# odrs_redraw.net
KiCad netlist of a schematic drawn in EAGLE
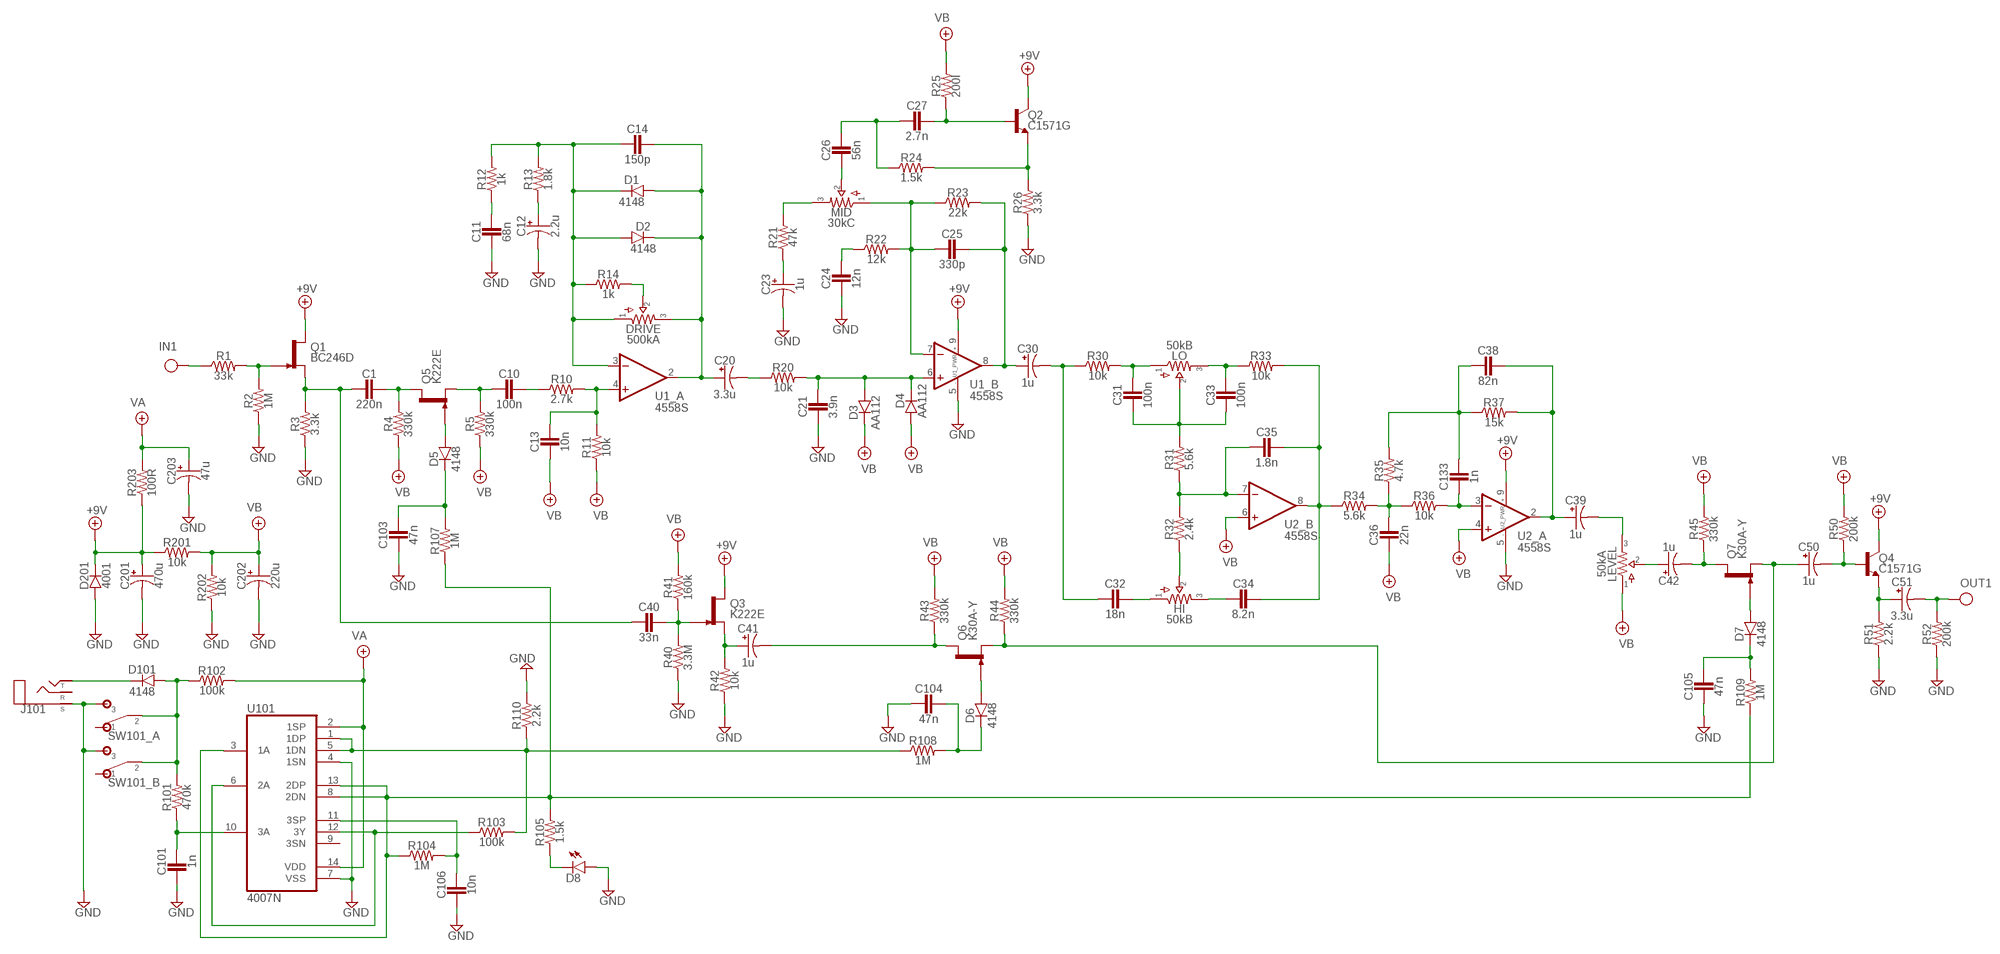
[diagram p0: schematic, sheet 1]

(export (version "E")
  (design (tool "Eeschema 10.0.6"))
  (components
    (comp (ref "C1")
      (value "220n")
      (footprint "eagle-import:BOX_SMALL")
      (libsource (lib "eagle-import") (part "CER/FILMBOX.1"))
    )
    (comp (ref "C10")
      (value "100n")
      (footprint "eagle-import:BOX_SMALL")
      (libsource (lib "eagle-import") (part "CER/FILMBOX.1"))
    )
    (comp (ref "C11")
      (value "68n")
      (footprint "eagle-import:BOX_SMALL")
      (libsource (lib "eagle-import") (part "CER/FILMBOX.1"))
    )
    (comp (ref "C12")
      (value "2.2u")
      (footprint "eagle-import:050_020")
      (libsource (lib "eagle-import") (part "0500"))
    )
    (comp (ref "C13")
      (value "10n")
      (footprint "eagle-import:BOX_SMALL")
      (libsource (lib "eagle-import") (part "CER/FILMBOX.1"))
    )
    (comp (ref "C14")
      (value "150p")
      (footprint "eagle-import:BOX_SMALL")
      (libsource (lib "eagle-import") (part "CER/FILMBOX.1"))
    )
    (comp (ref "C20")
      (value "3.3u")
      (footprint "eagle-import:050_020")
      (libsource (lib "eagle-import") (part "0500"))
    )
    (comp (ref "C21")
      (value "3.9n")
      (footprint "eagle-import:BOX_SMALL")
      (libsource (lib "eagle-import") (part "CER/FILMBOX.1"))
    )
    (comp (ref "C23")
      (value "1u")
      (footprint "eagle-import:050_020")
      (libsource (lib "eagle-import") (part "0500"))
    )
    (comp (ref "C24")
      (value "12n")
      (footprint "eagle-import:BOX_SMALL")
      (libsource (lib "eagle-import") (part "CER/FILMBOX.1"))
    )
    (comp (ref "C25")
      (value "330p")
      (footprint "eagle-import:BOX_SMALL")
      (libsource (lib "eagle-import") (part "CER/FILMBOX.1"))
    )
    (comp (ref "C26")
      (value "56n")
      (footprint "eagle-import:BOX_SMALL")
      (libsource (lib "eagle-import") (part "CER/FILMBOX.1"))
    )
    (comp (ref "C27")
      (value "2.7n")
      (footprint "eagle-import:BOX_SMALL")
      (libsource (lib "eagle-import") (part "CER/FILMBOX.1"))
    )
    (comp (ref "C30")
      (value "1u")
      (footprint "eagle-import:050_020")
      (libsource (lib "eagle-import") (part "0500"))
    )
    (comp (ref "C31")
      (value "100n")
      (footprint "eagle-import:BOX_SMALL")
      (libsource (lib "eagle-import") (part "CER/FILMBOX.1"))
    )
    (comp (ref "C32")
      (value "18n")
      (footprint "eagle-import:BOX_SMALL")
      (libsource (lib "eagle-import") (part "CER/FILMBOX.1"))
    )
    (comp (ref "C33")
      (value "100n")
      (footprint "eagle-import:BOX_SMALL")
      (libsource (lib "eagle-import") (part "CER/FILMBOX.1"))
    )
    (comp (ref "C34")
      (value "8.2n")
      (footprint "eagle-import:BOX_SMALL")
      (libsource (lib "eagle-import") (part "CER/FILMBOX.1"))
    )
    (comp (ref "C35")
      (value "1.8n")
      (footprint "eagle-import:BOX_SMALL")
      (libsource (lib "eagle-import") (part "CER/FILMBOX.1"))
    )
    (comp (ref "C36")
      (value "22n")
      (footprint "eagle-import:BOX_SMALL")
      (libsource (lib "eagle-import") (part "CER/FILMBOX.1"))
    )
    (comp (ref "C38")
      (value "82n")
      (footprint "eagle-import:BOX_SMALL")
      (libsource (lib "eagle-import") (part "CER/FILMBOX.1"))
    )
    (comp (ref "C39")
      (value "1u")
      (footprint "eagle-import:050_020")
      (libsource (lib "eagle-import") (part "0500"))
    )
    (comp (ref "C40")
      (value "33n")
      (footprint "eagle-import:BOX_SMALL")
      (libsource (lib "eagle-import") (part "CER/FILMBOX.1"))
    )
    (comp (ref "C41")
      (value "1u")
      (footprint "eagle-import:050_020")
      (libsource (lib "eagle-import") (part "0500"))
    )
    (comp (ref "C42")
      (value "1u")
      (footprint "eagle-import:050_020")
      (libsource (lib "eagle-import") (part "0500"))
    )
    (comp (ref "C50")
      (value "1u")
      (footprint "eagle-import:050_020")
      (libsource (lib "eagle-import") (part "0500"))
    )
    (comp (ref "C51")
      (value "3.3u")
      (footprint "eagle-import:050_020")
      (libsource (lib "eagle-import") (part "0500"))
    )
    (comp (ref "C101")
      (value "1n")
      (footprint "eagle-import:BOX_SMALL")
      (libsource (lib "eagle-import") (part "CER/FILMBOX.1"))
    )
    (comp (ref "C103")
      (value "47n")
      (footprint "eagle-import:BOX_SMALL")
      (libsource (lib "eagle-import") (part "CER/FILMBOX.1"))
    )
    (comp (ref "C104")
      (value "47n")
      (footprint "eagle-import:BOX_SMALL")
      (libsource (lib "eagle-import") (part "CER/FILMBOX.1"))
    )
    (comp (ref "C105")
      (value "47n")
      (footprint "eagle-import:BOX_SMALL")
      (libsource (lib "eagle-import") (part "CER/FILMBOX.1"))
    )
    (comp (ref "C106")
      (value "10n")
      (footprint "eagle-import:BOX_SMALL")
      (libsource (lib "eagle-import") (part "CER/FILMBOX.1"))
    )
    (comp (ref "C133")
      (value "1n")
      (footprint "eagle-import:BOX_SMALL")
      (libsource (lib "eagle-import") (part "CER/FILMBOX.1"))
    )
    (comp (ref "C201")
      (value "470u")
      (footprint "eagle-import:040_020")
      (libsource (lib "eagle-import") (part "0400"))
    )
    (comp (ref "C202")
      (value "220u")
      (footprint "eagle-import:040_020")
      (libsource (lib "eagle-import") (part "0400"))
    )
    (comp (ref "C203")
      (value "47u")
      (footprint "eagle-import:040_020")
      (libsource (lib "eagle-import") (part "0400"))
    )
    (comp (ref "D1")
      (value "4148")
      (footprint "eagle-import:DO35-2")
      (libsource (lib "eagle-import") (part "DO35.2"))
    )
    (comp (ref "D2")
      (value "4148")
      (footprint "eagle-import:DO35-2")
      (libsource (lib "eagle-import") (part "DO35.2"))
    )
    (comp (ref "D3")
      (value "AA112")
      (footprint "eagle-import:DO35-2")
      (libsource (lib "eagle-import") (part "DO35.2"))
    )
    (comp (ref "D4")
      (value "AA112")
      (footprint "eagle-import:DO35-2")
      (libsource (lib "eagle-import") (part "DO35.2"))
    )
    (comp (ref "D5")
      (value "4148")
      (footprint "eagle-import:DO35-2")
      (libsource (lib "eagle-import") (part "DO35.2"))
    )
    (comp (ref "D6")
      (value "4148")
      (footprint "eagle-import:DO35-2")
      (libsource (lib "eagle-import") (part "DO35.2"))
    )
    (comp (ref "D7")
      (value "4148")
      (footprint "eagle-import:DO35-2")
      (libsource (lib "eagle-import") (part "DO35.2"))
    )
    (comp (ref "D8")
      (value "LED")
      (footprint "eagle-import:3MM_D")
      (libsource (lib "eagle-import") (part "LED"))
    )
    (comp (ref "D101")
      (value "4148")
      (footprint "eagle-import:DO35-2")
      (libsource (lib "eagle-import") (part "DO35.2"))
    )
    (comp (ref "D201")
      (value "4001")
      (footprint "eagle-import:DO35-2")
      (libsource (lib "eagle-import") (part "DO35.2"))
    )
    (comp (ref "DRIVE")
      (value "500kA")
      (footprint "eagle-import:16MM")
      (libsource (lib "eagle-import") (part "POTS16MM"))
    )
    (comp (ref "HI")
      (value "50kB")
      (footprint "eagle-import:16MM")
      (libsource (lib "eagle-import") (part "POTS16MM"))
    )
    (comp (ref "J101")
      (value "STEREO3PADS")
      (footprint "eagle-import:THREEPADS")
      (libsource (lib "eagle-import") (part "STEREO3PADS"))
    )
    (comp (ref "LEVEL")
      (value "50kA")
      (footprint "eagle-import:16MM")
      (libsource (lib "eagle-import") (part "POTS16MM"))
    )
    (comp (ref "LO")
      (value "50kB")
      (footprint "eagle-import:16MM")
      (libsource (lib "eagle-import") (part "POTS16MM"))
    )
    (comp (ref "MID")
      (value "30kC")
      (footprint "eagle-import:16MM")
      (libsource (lib "eagle-import") (part "POTS16MM"))
    )
    (comp (ref "Q1")
      (value "BC246D")
      (footprint "eagle-import:TO92-")
      (libsource (lib "eagle-import") (part "2SK170"))
    )
    (comp (ref "Q2")
      (value "C1571G")
      (footprint "eagle-import:TO92-")
      (libsource (lib "eagle-import") (part "2N3904"))
    )
    (comp (ref "Q3")
      (value "K222E")
      (footprint "eagle-import:TO92-")
      (libsource (lib "eagle-import") (part "2SK170"))
    )
    (comp (ref "Q4")
      (value "C1571G")
      (footprint "eagle-import:TO92-")
      (libsource (lib "eagle-import") (part "2N3904"))
    )
    (comp (ref "Q5")
      (value "K222E")
      (footprint "eagle-import:TO92-")
      (libsource (lib "eagle-import") (part "2SK170"))
    )
    (comp (ref "Q6")
      (value "K30A-Y")
      (footprint "eagle-import:TO92-")
      (libsource (lib "eagle-import") (part "2SK170"))
    )
    (comp (ref "Q7")
      (value "K30A-Y")
      (footprint "eagle-import:TO92-")
      (libsource (lib "eagle-import") (part "2SK170"))
    )
    (comp (ref "R1")
      (value "33k")
      (footprint "eagle-import:R0207_3")
      (libsource (lib "eagle-import") (part "R_.3B"))
    )
    (comp (ref "R2")
      (value "1M")
      (footprint "eagle-import:R0207_3")
      (libsource (lib "eagle-import") (part "R_.3B"))
    )
    (comp (ref "R3")
      (value "3.3k")
      (footprint "eagle-import:R0207_3")
      (libsource (lib "eagle-import") (part "R_.3B"))
    )
    (comp (ref "R4")
      (value "330k")
      (footprint "eagle-import:R0207_3")
      (libsource (lib "eagle-import") (part "R_.3B"))
    )
    (comp (ref "R5")
      (value "330k")
      (footprint "eagle-import:R0207_3")
      (libsource (lib "eagle-import") (part "R_.3B"))
    )
    (comp (ref "R10")
      (value "2.7k")
      (footprint "eagle-import:R0207_3")
      (libsource (lib "eagle-import") (part "R_.3B"))
    )
    (comp (ref "R11")
      (value "10k")
      (footprint "eagle-import:R0207_3")
      (libsource (lib "eagle-import") (part "R_.3B"))
    )
    (comp (ref "R12")
      (value "1k")
      (footprint "eagle-import:R0207_3")
      (libsource (lib "eagle-import") (part "R_.3B"))
    )
    (comp (ref "R13")
      (value "1.8k")
      (footprint "eagle-import:R0207_3")
      (libsource (lib "eagle-import") (part "R_.3B"))
    )
    (comp (ref "R14")
      (value "1k")
      (footprint "eagle-import:R0207_3")
      (libsource (lib "eagle-import") (part "R_.3B"))
    )
    (comp (ref "R20")
      (value "10k")
      (footprint "eagle-import:R0207_3")
      (libsource (lib "eagle-import") (part "R_.3B"))
    )
    (comp (ref "R21")
      (value "47k")
      (footprint "eagle-import:R0207_3")
      (libsource (lib "eagle-import") (part "R_.3B"))
    )
    (comp (ref "R22")
      (value "12k")
      (footprint "eagle-import:R0207_3")
      (libsource (lib "eagle-import") (part "R_.3B"))
    )
    (comp (ref "R23")
      (value "22k")
      (footprint "eagle-import:R0207_3")
      (libsource (lib "eagle-import") (part "R_.3B"))
    )
    (comp (ref "R24")
      (value "1.5k")
      (footprint "eagle-import:R0207_3")
      (libsource (lib "eagle-import") (part "R_.3B"))
    )
    (comp (ref "R25")
      (value "200l")
      (footprint "eagle-import:R0207_3")
      (libsource (lib "eagle-import") (part "R_.3B"))
    )
    (comp (ref "R26")
      (value "3.3k")
      (footprint "eagle-import:R0207_3")
      (libsource (lib "eagle-import") (part "R_.3B"))
    )
    (comp (ref "R30")
      (value "10k")
      (footprint "eagle-import:R0207_3")
      (libsource (lib "eagle-import") (part "R_.3B"))
    )
    (comp (ref "R31")
      (value "5.6k")
      (footprint "eagle-import:R0207_3")
      (libsource (lib "eagle-import") (part "R_.3B"))
    )
    (comp (ref "R32")
      (value "2.4k")
      (footprint "eagle-import:R0207_3")
      (libsource (lib "eagle-import") (part "R_.3B"))
    )
    (comp (ref "R33")
      (value "10k")
      (footprint "eagle-import:R0207_3")
      (libsource (lib "eagle-import") (part "R_.3B"))
    )
    (comp (ref "R34")
      (value "5.6k")
      (footprint "eagle-import:R0207_3")
      (libsource (lib "eagle-import") (part "R_.3B"))
    )
    (comp (ref "R35")
      (value "4.7k")
      (footprint "eagle-import:R0207_3")
      (libsource (lib "eagle-import") (part "R_.3B"))
    )
    (comp (ref "R36")
      (value "10k")
      (footprint "eagle-import:R0207_3")
      (libsource (lib "eagle-import") (part "R_.3B"))
    )
    (comp (ref "R37")
      (value "15k")
      (footprint "eagle-import:R0207_3")
      (libsource (lib "eagle-import") (part "R_.3B"))
    )
    (comp (ref "R40")
      (value "3.3M")
      (footprint "eagle-import:R0207_3")
      (libsource (lib "eagle-import") (part "R_.3B"))
    )
    (comp (ref "R41")
      (value "160k")
      (footprint "eagle-import:R0207_3")
      (libsource (lib "eagle-import") (part "R_.3B"))
    )
    (comp (ref "R42")
      (value "10k")
      (footprint "eagle-import:R0207_3")
      (libsource (lib "eagle-import") (part "R_.3B"))
    )
    (comp (ref "R43")
      (value "330k")
      (footprint "eagle-import:R0207_3")
      (libsource (lib "eagle-import") (part "R_.3B"))
    )
    (comp (ref "R44")
      (value "330k")
      (footprint "eagle-import:R0207_3")
      (libsource (lib "eagle-import") (part "R_.3B"))
    )
    (comp (ref "R45")
      (value "330k")
      (footprint "eagle-import:R0207_3")
      (libsource (lib "eagle-import") (part "R_.3B"))
    )
    (comp (ref "R50")
      (value "200k")
      (footprint "eagle-import:R0207_3")
      (libsource (lib "eagle-import") (part "R_.3B"))
    )
    (comp (ref "R51")
      (value "2.2k")
      (footprint "eagle-import:R0207_3")
      (libsource (lib "eagle-import") (part "R_.3B"))
    )
    (comp (ref "R52")
      (value "200k")
      (footprint "eagle-import:R0207_3")
      (libsource (lib "eagle-import") (part "R_.3B"))
    )
    (comp (ref "R101")
      (value "470k")
      (footprint "eagle-import:R0207_3")
      (libsource (lib "eagle-import") (part "R_.3B"))
    )
    (comp (ref "R102")
      (value "100k")
      (footprint "eagle-import:R0207_3")
      (libsource (lib "eagle-import") (part "R_.3B"))
    )
    (comp (ref "R103")
      (value "100k")
      (footprint "eagle-import:R0207_3")
      (libsource (lib "eagle-import") (part "R_.3B"))
    )
    (comp (ref "R104")
      (value "1M")
      (footprint "eagle-import:R0207_3")
      (libsource (lib "eagle-import") (part "R_.3B"))
    )
    (comp (ref "R105")
      (value "1.5k")
      (footprint "eagle-import:R0207_3")
      (libsource (lib "eagle-import") (part "R_.3B"))
    )
    (comp (ref "R107")
      (value "1M")
      (footprint "eagle-import:R0207_3")
      (libsource (lib "eagle-import") (part "R_.3B"))
    )
    (comp (ref "R108")
      (value "1M")
      (footprint "eagle-import:R0207_3")
      (libsource (lib "eagle-import") (part "R_.3B"))
    )
    (comp (ref "R109")
      (value "1M")
      (footprint "eagle-import:R0207_3")
      (libsource (lib "eagle-import") (part "R_.3B"))
    )
    (comp (ref "R110")
      (value "2.2k")
      (footprint "eagle-import:R0207_3")
      (libsource (lib "eagle-import") (part "R_.3B"))
    )
    (comp (ref "R201")
      (value "10k")
      (footprint "eagle-import:R0207_3")
      (libsource (lib "eagle-import") (part "R_.3B"))
    )
    (comp (ref "R202")
      (value "10k")
      (footprint "eagle-import:R0207_3")
      (libsource (lib "eagle-import") (part "R_.3B"))
    )
    (comp (ref "R203")
      (value "100R")
      (footprint "eagle-import:R0207_3")
      (libsource (lib "eagle-import") (part "R_.3B"))
    )
    (comp (ref "SW101")
      (value "DPDT")
      (footprint "eagle-import:DPDT")
      (libsource (lib "eagle-import") (part "DPDT"))
    )
    (comp (ref "U1")
      (value "4558S")
      (footprint "eagle-import:SIL09")
      (libsource (lib "eagle-import") (part "DUAL"))
    )
    (comp (ref "U2")
      (value "4558S")
      (footprint "eagle-import:SIL09")
      (libsource (lib "eagle-import") (part "DUAL"))
    )
    (comp (ref "U101")
      (value "4007N")
      (footprint "eagle-import:DIL14")
      (libsource (lib "eagle-import") (part "4007N"))
    )
  )
  (nets
    (net (code "1") (name "+9V") (class "Default")
      (node (ref "C201") (pin "+") (pinfunction "+_+") (pintype "passive"))
      (node (ref "D201") (pin "C") (pinfunction "C_C") (pintype "passive"))
      (node (ref "Q1") (pin "3") (pinfunction "D_3") (pintype "passive"))
      (node (ref "Q2") (pin "1") (pinfunction "C_1") (pintype "passive"))
      (node (ref "Q3") (pin "3") (pinfunction "D_3") (pintype "passive"))
      (node (ref "Q4") (pin "1") (pinfunction "C_1") (pintype "passive"))
      (node (ref "R201") (pin "1") (pinfunction "1_1") (pintype "passive"))
      (node (ref "R203") (pin "1") (pinfunction "1_1") (pintype "passive"))
      (node (ref "U1") (pin "9") (pinfunction "V+_9") (pintype "power_in"))
      (node (ref "U2") (pin "9") (pinfunction "V+_9") (pintype "power_in"))
    )
    (net (code "2") (name "GND") (class "Default")
      (node (ref "C101") (pin "2") (pinfunction "2_2") (pintype "passive"))
      (node (ref "C103") (pin "2") (pinfunction "2_2") (pintype "passive"))
      (node (ref "C104") (pin "2") (pinfunction "2_2") (pintype "passive"))
      (node (ref "C105") (pin "2") (pinfunction "2_2") (pintype "passive"))
      (node (ref "C106") (pin "2") (pinfunction "2_2") (pintype "passive"))
      (node (ref "C11") (pin "2") (pinfunction "2_2") (pintype "passive"))
      (node (ref "C12") (pin "-") (pinfunction "-_-") (pintype "passive"))
      (node (ref "C201") (pin "-") (pinfunction "-_-") (pintype "passive"))
      (node (ref "C202") (pin "-") (pinfunction "-_-") (pintype "passive"))
      (node (ref "C203") (pin "-") (pinfunction "-_-") (pintype "passive"))
      (node (ref "C21") (pin "2") (pinfunction "2_2") (pintype "passive"))
      (node (ref "C23") (pin "-") (pinfunction "-_-") (pintype "passive"))
      (node (ref "C24") (pin "2") (pinfunction "2_2") (pintype "passive"))
      (node (ref "D201") (pin "A") (pinfunction "A_A") (pintype "passive"))
      (node (ref "D8") (pin "ANODE") (pinfunction "A_ANODE") (pintype "passive"))
      (node (ref "J101") (pin "SLEEVE") (pinfunction "S_SLEEVE") (pintype "passive"))
      (node (ref "R110") (pin "2") (pinfunction "2_2") (pintype "passive"))
      (node (ref "R2") (pin "1") (pinfunction "1_1") (pintype "passive"))
      (node (ref "R202") (pin "1") (pinfunction "1_1") (pintype "passive"))
      (node (ref "R26") (pin "1") (pinfunction "1_1") (pintype "passive"))
      (node (ref "R3") (pin "1") (pinfunction "1_1") (pintype "passive"))
      (node (ref "R40") (pin "1") (pinfunction "1_1") (pintype "passive"))
      (node (ref "R42") (pin "1") (pinfunction "1_1") (pintype "passive"))
      (node (ref "R51") (pin "1") (pinfunction "1_1") (pintype "passive"))
      (node (ref "R52") (pin "1") (pinfunction "1_1") (pintype "passive"))
      (node (ref "SW101") (pin "A3") (pinfunction "3_A3") (pintype "passive"))
      (node (ref "SW101") (pin "B3") (pinfunction "3_B3") (pintype "passive"))
      (node (ref "U1") (pin "5") (pinfunction "V-_5") (pintype "power_in"))
      (node (ref "U101") (pin "4") (pinfunction "1SN_4") (pintype "open_collector"))
      (node (ref "U101") (pin "7") (pinfunction "VSS_7") (pintype "input"))
      (node (ref "U2") (pin "5") (pinfunction "V-_5") (pintype "power_in"))
    )
    (net (code "3") (name "IN") (class "Default")
      (node (ref "R1") (pin "1") (pinfunction "1_1") (pintype "passive"))
    )
    (net (code "4") (name "Net-(C10-Pad1)") (class "Default")
      (node (ref "C10") (pin "1") (pinfunction "1_1") (pintype "passive"))
      (node (ref "R10") (pin "1") (pinfunction "1_1") (pintype "passive"))
    )
    (net (code "5") (name "Net-(C11-Pad1)") (class "Default")
      (node (ref "C11") (pin "1") (pinfunction "1_1") (pintype "passive"))
      (node (ref "R12") (pin "1") (pinfunction "1_1") (pintype "passive"))
    )
    (net (code "6") (name "Net-(C12-Pad+)") (class "Default")
      (node (ref "C12") (pin "+") (pinfunction "+_+") (pintype "passive"))
      (node (ref "R13") (pin "1") (pinfunction "1_1") (pintype "passive"))
    )
    (net (code "7") (name "Net-(C20-Pad-)") (class "Default")
      (node (ref "C20") (pin "-") (pinfunction "-_-") (pintype "passive"))
      (node (ref "R20") (pin "1") (pinfunction "1_1") (pintype "passive"))
    )
    (net (code "8") (name "Net-(C23-Pad+)") (class "Default")
      (node (ref "C23") (pin "+") (pinfunction "+_+") (pintype "passive"))
      (node (ref "R21") (pin "1") (pinfunction "1_1") (pintype "passive"))
    )
    (net (code "9") (name "Net-(C24-Pad1)") (class "Default")
      (node (ref "C24") (pin "1") (pinfunction "1_1") (pintype "passive"))
      (node (ref "R22") (pin "1") (pinfunction "1_1") (pintype "passive"))
    )
    (net (code "10") (name "Net-(C26-Pad1)") (class "Default")
      (node (ref "C26") (pin "1") (pinfunction "1_1") (pintype "passive"))
      (node (ref "C27") (pin "2") (pinfunction "2_2") (pintype "passive"))
      (node (ref "R24") (pin "1") (pinfunction "1_1") (pintype "passive"))
    )
    (net (code "11") (name "Net-(C26-Pad2)") (class "Default")
      (node (ref "C26") (pin "2") (pinfunction "2_2") (pintype "passive"))
      (node (ref "MID") (pin "2") (pinfunction "2_2") (pintype "passive"))
    )
    (net (code "12") (name "Net-(C30-Pad-)") (class "Default")
      (node (ref "C30") (pin "-") (pinfunction "-_-") (pintype "passive"))
      (node (ref "C32") (pin "2") (pinfunction "2_2") (pintype "passive"))
      (node (ref "R30") (pin "1") (pinfunction "1_1") (pintype "passive"))
    )
    (net (code "13") (name "Net-(C31-Pad1)") (class "Default")
      (node (ref "C31") (pin "1") (pinfunction "1_1") (pintype "passive"))
      (node (ref "LO") (pin "1") (pinfunction "1_1") (pintype "passive"))
      (node (ref "R30") (pin "2") (pinfunction "2_2") (pintype "passive"))
    )
    (net (code "14") (name "Net-(C31-Pad2)") (class "Default")
      (node (ref "C31") (pin "2") (pinfunction "2_2") (pintype "passive"))
      (node (ref "C33") (pin "2") (pinfunction "2_2") (pintype "passive"))
      (node (ref "LO") (pin "2") (pinfunction "2_2") (pintype "passive"))
      (node (ref "R31") (pin "2") (pinfunction "2_2") (pintype "passive"))
    )
    (net (code "15") (name "Net-(C32-Pad1)") (class "Default")
      (node (ref "C32") (pin "1") (pinfunction "1_1") (pintype "passive"))
      (node (ref "HI") (pin "1") (pinfunction "1_1") (pintype "passive"))
    )
    (net (code "16") (name "Net-(C33-Pad1)") (class "Default")
      (node (ref "C33") (pin "1") (pinfunction "1_1") (pintype "passive"))
      (node (ref "LO") (pin "3") (pinfunction "3_3") (pintype "passive"))
      (node (ref "R33") (pin "1") (pinfunction "1_1") (pintype "passive"))
    )
    (net (code "17") (name "Net-(C34-Pad2)") (class "Default")
      (node (ref "C34") (pin "2") (pinfunction "2_2") (pintype "passive"))
      (node (ref "HI") (pin "3") (pinfunction "3_3") (pintype "passive"))
    )
    (net (code "18") (name "Net-(C36-Pad1)") (class "Default")
      (node (ref "C36") (pin "1") (pinfunction "1_1") (pintype "passive"))
      (node (ref "R34") (pin "2") (pinfunction "2_2") (pintype "passive"))
      (node (ref "R35") (pin "1") (pinfunction "1_1") (pintype "passive"))
      (node (ref "R36") (pin "1") (pinfunction "1_1") (pintype "passive"))
    )
    (net (code "19") (name "Net-(C39-Pad-)") (class "Default")
      (node (ref "C39") (pin "-") (pinfunction "-_-") (pintype "passive"))
      (node (ref "LEVEL") (pin "3") (pinfunction "3_3") (pintype "passive"))
    )
    (net (code "20") (name "Net-(C42-Pad+)") (class "Default")
      (node (ref "C42") (pin "+") (pinfunction "+_+") (pintype "passive"))
      (node (ref "LEVEL") (pin "2") (pinfunction "2_2") (pintype "passive"))
    )
    (net (code "21") (name "Net-(C103-Pad1)") (class "Default")
      (node (ref "C103") (pin "1") (pinfunction "1_1") (pintype "passive"))
      (node (ref "D5") (pin "C") (pinfunction "C_C") (pintype "passive"))
      (node (ref "R107") (pin "2") (pinfunction "2_2") (pintype "passive"))
    )
    (net (code "22") (name "Net-(C104-Pad1)") (class "Default")
      (node (ref "C104") (pin "1") (pinfunction "1_1") (pintype "passive"))
      (node (ref "D6") (pin "C") (pinfunction "C_C") (pintype "passive"))
      (node (ref "R108") (pin "2") (pinfunction "2_2") (pintype "passive"))
    )
    (net (code "23") (name "Net-(C105-Pad1)") (class "Default")
      (node (ref "C105") (pin "1") (pinfunction "1_1") (pintype "passive"))
      (node (ref "D7") (pin "C") (pinfunction "C_C") (pintype "passive"))
      (node (ref "R109") (pin "2") (pinfunction "2_2") (pintype "passive"))
    )
    (net (code "24") (name "Net-(C133-Pad1)") (class "Default")
      (node (ref "C133") (pin "1") (pinfunction "1_1") (pintype "passive"))
      (node (ref "C38") (pin "2") (pinfunction "2_2") (pintype "passive"))
      (node (ref "R35") (pin "2") (pinfunction "2_2") (pintype "passive"))
      (node (ref "R37") (pin "1") (pinfunction "1_1") (pintype "passive"))
    )
    (net (code "25") (name "Net-(D8-C)") (class "Default")
      (node (ref "D8") (pin "P$1") (pinfunction "C_P$1") (pintype "passive"))
      (node (ref "R105") (pin "1") (pinfunction "1_1") (pintype "passive"))
    )
    (net (code "26") (name "Net-(DRIVE-Pad2)") (class "Default")
      (node (ref "DRIVE") (pin "2") (pinfunction "2_2") (pintype "passive"))
      (node (ref "R14") (pin "2") (pinfunction "2_2") (pintype "passive"))
    )
    (net (code "27") (name "Net-(HI-Pad2)") (class "Default")
      (node (ref "HI") (pin "2") (pinfunction "2_2") (pintype "passive"))
      (node (ref "R32") (pin "1") (pinfunction "1_1") (pintype "passive"))
    )
    (net (code "28") (name "Net-(J101-T)") (class "Default")
      (node (ref "D101") (pin "C") (pinfunction "C_C") (pintype "passive"))
      (node (ref "J101") (pin "TIP") (pinfunction "T_TIP") (pintype "passive"))
    )
    (net (code "29") (name "Net-(MID-Pad3)") (class "Default")
      (node (ref "MID") (pin "3") (pinfunction "3_3") (pintype "passive"))
      (node (ref "R21") (pin "2") (pinfunction "2_2") (pintype "passive"))
    )
    (net (code "30") (name "Net-(Q1-G)") (class "Default")
      (node (ref "Q1") (pin "2") (pinfunction "G_2") (pintype "passive"))
      (node (ref "R1") (pin "2") (pinfunction "2_2") (pintype "passive"))
      (node (ref "R2") (pin "2") (pinfunction "2_2") (pintype "passive"))
    )
    (net (code "31") (name "Net-(Q1-S)") (class "Default")
      (node (ref "C1") (pin "2") (pinfunction "2_2") (pintype "passive"))
      (node (ref "C40") (pin "2") (pinfunction "2_2") (pintype "passive"))
      (node (ref "Q1") (pin "1") (pinfunction "S_1") (pintype "passive"))
      (node (ref "R3") (pin "2") (pinfunction "2_2") (pintype "passive"))
    )
    (net (code "32") (name "Net-(Q2-B)") (class "Default")
      (node (ref "C27") (pin "1") (pinfunction "1_1") (pintype "passive"))
      (node (ref "Q2") (pin "2") (pinfunction "B_2") (pintype "passive"))
      (node (ref "R25") (pin "1") (pinfunction "1_1") (pintype "passive"))
    )
    (net (code "33") (name "Net-(Q2-E)") (class "Default")
      (node (ref "Q2") (pin "3") (pinfunction "E_3") (pintype "passive"))
      (node (ref "R24") (pin "2") (pinfunction "2_2") (pintype "passive"))
      (node (ref "R26") (pin "2") (pinfunction "2_2") (pintype "passive"))
    )
    (net (code "34") (name "Net-(Q3-G)") (class "Default")
      (node (ref "C40") (pin "1") (pinfunction "1_1") (pintype "passive"))
      (node (ref "Q3") (pin "2") (pinfunction "G_2") (pintype "passive"))
      (node (ref "R40") (pin "2") (pinfunction "2_2") (pintype "passive"))
      (node (ref "R41") (pin "1") (pinfunction "1_1") (pintype "passive"))
    )
    (net (code "35") (name "Net-(Q3-S)") (class "Default")
      (node (ref "C41") (pin "+") (pinfunction "+_+") (pintype "passive"))
      (node (ref "Q3") (pin "1") (pinfunction "S_1") (pintype "passive"))
      (node (ref "R42") (pin "2") (pinfunction "2_2") (pintype "passive"))
    )
    (net (code "36") (name "Net-(Q4-B)") (class "Default")
      (node (ref "C50") (pin "-") (pinfunction "-_-") (pintype "passive"))
      (node (ref "Q4") (pin "2") (pinfunction "B_2") (pintype "passive"))
      (node (ref "R50") (pin "1") (pinfunction "1_1") (pintype "passive"))
    )
    (net (code "37") (name "Net-(Q4-E)") (class "Default")
      (node (ref "C51") (pin "+") (pinfunction "+_+") (pintype "passive"))
      (node (ref "Q4") (pin "3") (pinfunction "E_3") (pintype "passive"))
      (node (ref "R51") (pin "2") (pinfunction "2_2") (pintype "passive"))
    )
    (net (code "38") (name "Net-(Q5-D)") (class "Default")
      (node (ref "C1") (pin "1") (pinfunction "1_1") (pintype "passive"))
      (node (ref "Q5") (pin "3") (pinfunction "D_3") (pintype "passive"))
      (node (ref "R4") (pin "2") (pinfunction "2_2") (pintype "passive"))
    )
    (net (code "39") (name "Net-(Q5-G)") (class "Default")
      (node (ref "D5") (pin "A") (pinfunction "A_A") (pintype "passive"))
      (node (ref "Q5") (pin "2") (pinfunction "G_2") (pintype "passive"))
    )
    (net (code "40") (name "Net-(Q5-S)") (class "Default")
      (node (ref "C10") (pin "2") (pinfunction "2_2") (pintype "passive"))
      (node (ref "Q5") (pin "1") (pinfunction "S_1") (pintype "passive"))
      (node (ref "R5") (pin "2") (pinfunction "2_2") (pintype "passive"))
    )
    (net (code "41") (name "Net-(Q6-D)") (class "Default")
      (node (ref "C41") (pin "-") (pinfunction "-_-") (pintype "passive"))
      (node (ref "Q6") (pin "3") (pinfunction "D_3") (pintype "passive"))
      (node (ref "R43") (pin "1") (pinfunction "1_1") (pintype "passive"))
    )
    (net (code "42") (name "Net-(Q6-G)") (class "Default")
      (node (ref "D6") (pin "A") (pinfunction "A_A") (pintype "passive"))
      (node (ref "Q6") (pin "2") (pinfunction "G_2") (pintype "passive"))
    )
    (net (code "43") (name "Net-(Q6-S)") (class "Default")
      (node (ref "C50") (pin "+") (pinfunction "+_+") (pintype "passive"))
      (node (ref "Q6") (pin "1") (pinfunction "S_1") (pintype "passive"))
      (node (ref "Q7") (pin "1") (pinfunction "S_1") (pintype "passive"))
      (node (ref "R44") (pin "1") (pinfunction "1_1") (pintype "passive"))
    )
    (net (code "44") (name "Net-(Q7-D)") (class "Default")
      (node (ref "C42") (pin "-") (pinfunction "-_-") (pintype "passive"))
      (node (ref "Q7") (pin "3") (pinfunction "D_3") (pintype "passive"))
      (node (ref "R45") (pin "1") (pinfunction "1_1") (pintype "passive"))
    )
    (net (code "45") (name "Net-(Q7-G)") (class "Default")
      (node (ref "D7") (pin "A") (pinfunction "A_A") (pintype "passive"))
      (node (ref "Q7") (pin "2") (pinfunction "G_2") (pintype "passive"))
    )
    (net (code "46") (name "Net-(SW101A-2)") (class "Default")
      (node (ref "D101") (pin "A") (pinfunction "A_A") (pintype "passive"))
      (node (ref "R101") (pin "2") (pinfunction "2_2") (pintype "passive"))
      (node (ref "R102") (pin "1") (pinfunction "1_1") (pintype "passive"))
      (node (ref "SW101") (pin "A2") (pinfunction "2_A2") (pintype "passive"))
      (node (ref "SW101") (pin "B2") (pinfunction "2_B2") (pintype "passive"))
    )
    (net (code "47") (name "Net-(U1A-+IN)") (class "Default")
      (node (ref "C13") (pin "1") (pinfunction "1_1") (pintype "passive"))
      (node (ref "R10") (pin "2") (pinfunction "2_2") (pintype "passive"))
      (node (ref "R11") (pin "2") (pinfunction "2_2") (pintype "passive"))
      (node (ref "U1") (pin "4") (pinfunction "+IN_4") (pintype "input"))
    )
    (net (code "48") (name "Net-(U1A--IN)") (class "Default")
      (node (ref "C14") (pin "2") (pinfunction "2_2") (pintype "passive"))
      (node (ref "D1") (pin "C") (pinfunction "C_C") (pintype "passive"))
      (node (ref "D2") (pin "A") (pinfunction "A_A") (pintype "passive"))
      (node (ref "DRIVE") (pin "1") (pinfunction "1_1") (pintype "passive"))
      (node (ref "R12") (pin "2") (pinfunction "2_2") (pintype "passive"))
      (node (ref "R13") (pin "2") (pinfunction "2_2") (pintype "passive"))
      (node (ref "R14") (pin "1") (pinfunction "1_1") (pintype "passive"))
      (node (ref "U1") (pin "3") (pinfunction "-IN_3") (pintype "input"))
    )
    (net (code "49") (name "Net-(U1A-OUT)") (class "Default")
      (node (ref "C14") (pin "1") (pinfunction "1_1") (pintype "passive"))
      (node (ref "C20") (pin "+") (pinfunction "+_+") (pintype "passive"))
      (node (ref "D1") (pin "A") (pinfunction "A_A") (pintype "passive"))
      (node (ref "D2") (pin "C") (pinfunction "C_C") (pintype "passive"))
      (node (ref "DRIVE") (pin "3") (pinfunction "3_3") (pintype "passive"))
      (node (ref "U1") (pin "2") (pinfunction "OUT_2") (pintype "output"))
    )
    (net (code "50") (name "Net-(U1B-+IN)") (class "Default")
      (node (ref "C21") (pin "1") (pinfunction "1_1") (pintype "passive"))
      (node (ref "D3") (pin "A") (pinfunction "A_A") (pintype "passive"))
      (node (ref "D4") (pin "C") (pinfunction "C_C") (pintype "passive"))
      (node (ref "R20") (pin "2") (pinfunction "2_2") (pintype "passive"))
      (node (ref "U1") (pin "6") (pinfunction "+IN_6") (pintype "input"))
    )
    (net (code "51") (name "Net-(U1B--IN)") (class "Default")
      (node (ref "C25") (pin "2") (pinfunction "2_2") (pintype "passive"))
      (node (ref "MID") (pin "1") (pinfunction "1_1") (pintype "passive"))
      (node (ref "R22") (pin "2") (pinfunction "2_2") (pintype "passive"))
      (node (ref "R23") (pin "1") (pinfunction "1_1") (pintype "passive"))
      (node (ref "U1") (pin "7") (pinfunction "-IN_7") (pintype "input"))
    )
    (net (code "52") (name "Net-(U1B-OUT)") (class "Default")
      (node (ref "C25") (pin "1") (pinfunction "1_1") (pintype "passive"))
      (node (ref "C30") (pin "+") (pinfunction "+_+") (pintype "passive"))
      (node (ref "R23") (pin "2") (pinfunction "2_2") (pintype "passive"))
      (node (ref "U1") (pin "8") (pinfunction "OUT_8") (pintype "output"))
    )
    (net (code "53") (name "Net-(U2A--IN)") (class "Default")
      (node (ref "C133") (pin "2") (pinfunction "2_2") (pintype "passive"))
      (node (ref "R36") (pin "2") (pinfunction "2_2") (pintype "passive"))
      (node (ref "U2") (pin "3") (pinfunction "-IN_3") (pintype "input"))
    )
    (net (code "54") (name "Net-(U2A-OUT)") (class "Default")
      (node (ref "C38") (pin "1") (pinfunction "1_1") (pintype "passive"))
      (node (ref "C39") (pin "+") (pinfunction "+_+") (pintype "passive"))
      (node (ref "R37") (pin "2") (pinfunction "2_2") (pintype "passive"))
      (node (ref "U2") (pin "2") (pinfunction "OUT_2") (pintype "output"))
    )
    (net (code "55") (name "Net-(U2B--IN)") (class "Default")
      (node (ref "C35") (pin "2") (pinfunction "2_2") (pintype "passive"))
      (node (ref "R31") (pin "1") (pinfunction "1_1") (pintype "passive"))
      (node (ref "R32") (pin "2") (pinfunction "2_2") (pintype "passive"))
      (node (ref "U2") (pin "7") (pinfunction "-IN_7") (pintype "input"))
    )
    (net (code "56") (name "Net-(U2B-OUT)") (class "Default")
      (node (ref "C34") (pin "1") (pinfunction "1_1") (pintype "passive"))
      (node (ref "C35") (pin "1") (pinfunction "1_1") (pintype "passive"))
      (node (ref "R33") (pin "2") (pinfunction "2_2") (pintype "passive"))
      (node (ref "R34") (pin "1") (pinfunction "1_1") (pintype "passive"))
      (node (ref "U2") (pin "8") (pinfunction "OUT_8") (pintype "output"))
    )
    (net (code "57") (name "Net-(U101-1A)") (class "Default")
      (node (ref "R104") (pin "1") (pinfunction "1_1") (pintype "passive"))
      (node (ref "R105") (pin "2") (pinfunction "2_2") (pintype "passive"))
      (node (ref "R107") (pin "1") (pinfunction "1_1") (pintype "passive"))
      (node (ref "R109") (pin "1") (pinfunction "1_1") (pintype "passive"))
      (node (ref "U101") (pin "13") (pinfunction "2DP_13") (pintype "bidirectional"))
      (node (ref "U101") (pin "3") (pinfunction "1A_3") (pintype "input"))
      (node (ref "U101") (pin "8") (pinfunction "2DN_8") (pintype "bidirectional"))
    )
    (net (code "58") (name "Net-(U101-1DN)") (class "Default")
      (node (ref "R103") (pin "2") (pinfunction "2_2") (pintype "passive"))
      (node (ref "R108") (pin "1") (pinfunction "1_1") (pintype "passive"))
      (node (ref "R110") (pin "1") (pinfunction "1_1") (pintype "passive"))
      (node (ref "U101") (pin "1") (pinfunction "1DP_1") (pintype "open_collector"))
      (node (ref "U101") (pin "5") (pinfunction "1DN_5") (pintype "open_collector"))
    )
    (net (code "59") (name "Net-(U101-2A)") (class "Default")
      (node (ref "R103") (pin "1") (pinfunction "1_1") (pintype "passive"))
      (node (ref "U101") (pin "12") (pinfunction "3Y_12") (pintype "bidirectional"))
      (node (ref "U101") (pin "6") (pinfunction "2A_6") (pintype "input"))
    )
    (net (code "60") (name "Net-(U101-3A)") (class "Default")
      (node (ref "C101") (pin "1") (pinfunction "1_1") (pintype "passive"))
      (node (ref "R101") (pin "1") (pinfunction "1_1") (pintype "passive"))
      (node (ref "U101") (pin "10") (pinfunction "3A_10") (pintype "input"))
    )
    (net (code "61") (name "Net-(U101-3SP)") (class "Default")
      (node (ref "C106") (pin "1") (pinfunction "1_1") (pintype "passive"))
      (node (ref "R104") (pin "2") (pinfunction "2_2") (pintype "passive"))
      (node (ref "U101") (pin "11") (pinfunction "3SP_11") (pintype "bidirectional"))
    )
    (net (code "62") (name "OUT") (class "Default")
      (node (ref "C51") (pin "-") (pinfunction "-_-") (pintype "passive"))
      (node (ref "R52") (pin "2") (pinfunction "2_2") (pintype "passive"))
    )
    (net (code "63") (name "VA") (class "Default")
      (node (ref "C203") (pin "+") (pinfunction "+_+") (pintype "passive"))
      (node (ref "R102") (pin "2") (pinfunction "2_2") (pintype "passive"))
      (node (ref "R203") (pin "2") (pinfunction "2_2") (pintype "passive"))
      (node (ref "U101") (pin "14") (pinfunction "VDD_14") (pintype "input"))
      (node (ref "U101") (pin "2") (pinfunction "1SP_2") (pintype "open_collector"))
    )
    (net (code "64") (name "VB") (class "Default")
      (node (ref "C13") (pin "2") (pinfunction "2_2") (pintype "passive"))
      (node (ref "C202") (pin "+") (pinfunction "+_+") (pintype "passive"))
      (node (ref "C36") (pin "2") (pinfunction "2_2") (pintype "passive"))
      (node (ref "D3") (pin "C") (pinfunction "C_C") (pintype "passive"))
      (node (ref "D4") (pin "A") (pinfunction "A_A") (pintype "passive"))
      (node (ref "LEVEL") (pin "1") (pinfunction "1_1") (pintype "passive"))
      (node (ref "R11") (pin "1") (pinfunction "1_1") (pintype "passive"))
      (node (ref "R201") (pin "2") (pinfunction "2_2") (pintype "passive"))
      (node (ref "R202") (pin "2") (pinfunction "2_2") (pintype "passive"))
      (node (ref "R25") (pin "2") (pinfunction "2_2") (pintype "passive"))
      (node (ref "R4") (pin "1") (pinfunction "1_1") (pintype "passive"))
      (node (ref "R41") (pin "2") (pinfunction "2_2") (pintype "passive"))
      (node (ref "R43") (pin "2") (pinfunction "2_2") (pintype "passive"))
      (node (ref "R44") (pin "2") (pinfunction "2_2") (pintype "passive"))
      (node (ref "R45") (pin "2") (pinfunction "2_2") (pintype "passive"))
      (node (ref "R5") (pin "1") (pinfunction "1_1") (pintype "passive"))
      (node (ref "R50") (pin "2") (pinfunction "2_2") (pintype "passive"))
      (node (ref "U2") (pin "4") (pinfunction "+IN_4") (pintype "input"))
      (node (ref "U2") (pin "6") (pinfunction "+IN_6") (pintype "input"))
    )
    (net (code "65") (name "unconnected-(J101-R-PadRING)") (class "Default")
      (node (ref "J101") (pin "RING") (pinfunction "R_RING") (pintype "passive"))
    )
    (net (code "66") (name "unconnected-(SW101A-1-PadA1)") (class "Default")
      (node (ref "SW101") (pin "A1") (pinfunction "1_A1") (pintype "passive"))
    )
    (net (code "67") (name "unconnected-(SW101B-1-PadB1)") (class "Default")
      (node (ref "SW101") (pin "B1") (pinfunction "1_B1") (pintype "passive"))
    )
    (net (code "68") (name "unconnected-(U101-3SN-Pad9)") (class "Default")
      (node (ref "U101") (pin "9") (pinfunction "3SN_9") (pintype "bidirectional"))
    )
  )
)
